# V1_0.net
KiCad netlist of a schematic drawn in Altium Designer
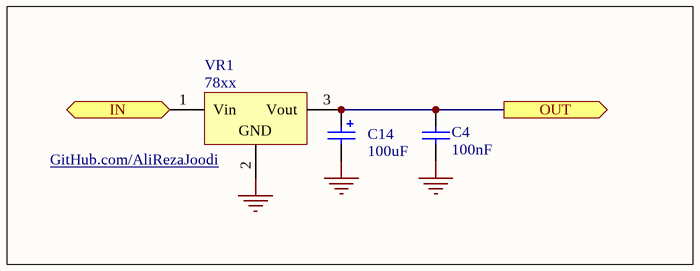
[diagram p0: V1.0.SchDoc]

(export (version "E")
  (design (tool "Eeschema 10.0.6"))
  (components
    (comp (ref "C4")
      (value "100nF")
      (footprint "CAPNTO2.54-3.05x1.78A")
      (description "Capacitor")
      (fields (field (name "MANUFACTURER") "Generic Components") (field (name "PUBLISHER") "Altium Limited"))
      (libsource (lib "Miscellaneous Devices") (part "Cap"))
    )
    (comp (ref "C14")
      (value "100uF")
      (footprint "CAPPR2.5-6.3x5")
      (description "Polarized Capacitor (Radial)")
      (fields (field (name "MANUFACTURER") "Generic Components") (field (name "PUBLISHER") "Altium Limited"))
      (libsource (lib "Miscellaneous Devices") (part "Cap Pol1"))
    )
    (comp (ref "VR1")
      (value "78xx")
      (footprint "TO220V")
      (description "Voltage Regulator")
      (fields (field (name "MANUFACTURER") "Generic Components") (field (name "PUBLISHER") "Altium Limited"))
      (libsource (lib "my Libraries") (part "Volt Reg"))
    )
  )
  (nets
    (net (code "1") (name "/IN") (class "Default")
      (node (ref "VR1") (pin "1") (pinfunction "Vin_1") (pintype "passive"))
    )
    (net (code "2") (name "/OUT") (class "Default")
      (node (ref "C14") (pin "1") (pinfunction "1_1") (pintype "passive"))
      (node (ref "C4") (pin "2") (pinfunction "2_2") (pintype "passive"))
      (node (ref "VR1") (pin "3") (pinfunction "Vout_3") (pintype "passive"))
    )
    (net (code "3") (name "GND") (class "Default")
      (node (ref "C14") (pin "2") (pinfunction "2_2") (pintype "passive"))
      (node (ref "C4") (pin "1") (pinfunction "1_1") (pintype "passive"))
      (node (ref "VR1") (pin "2") (pinfunction "GND_2") (pintype "passive"))
    )
  )
)
